# W601X.net
KiCad netlist of a schematic drawn in EAGLE
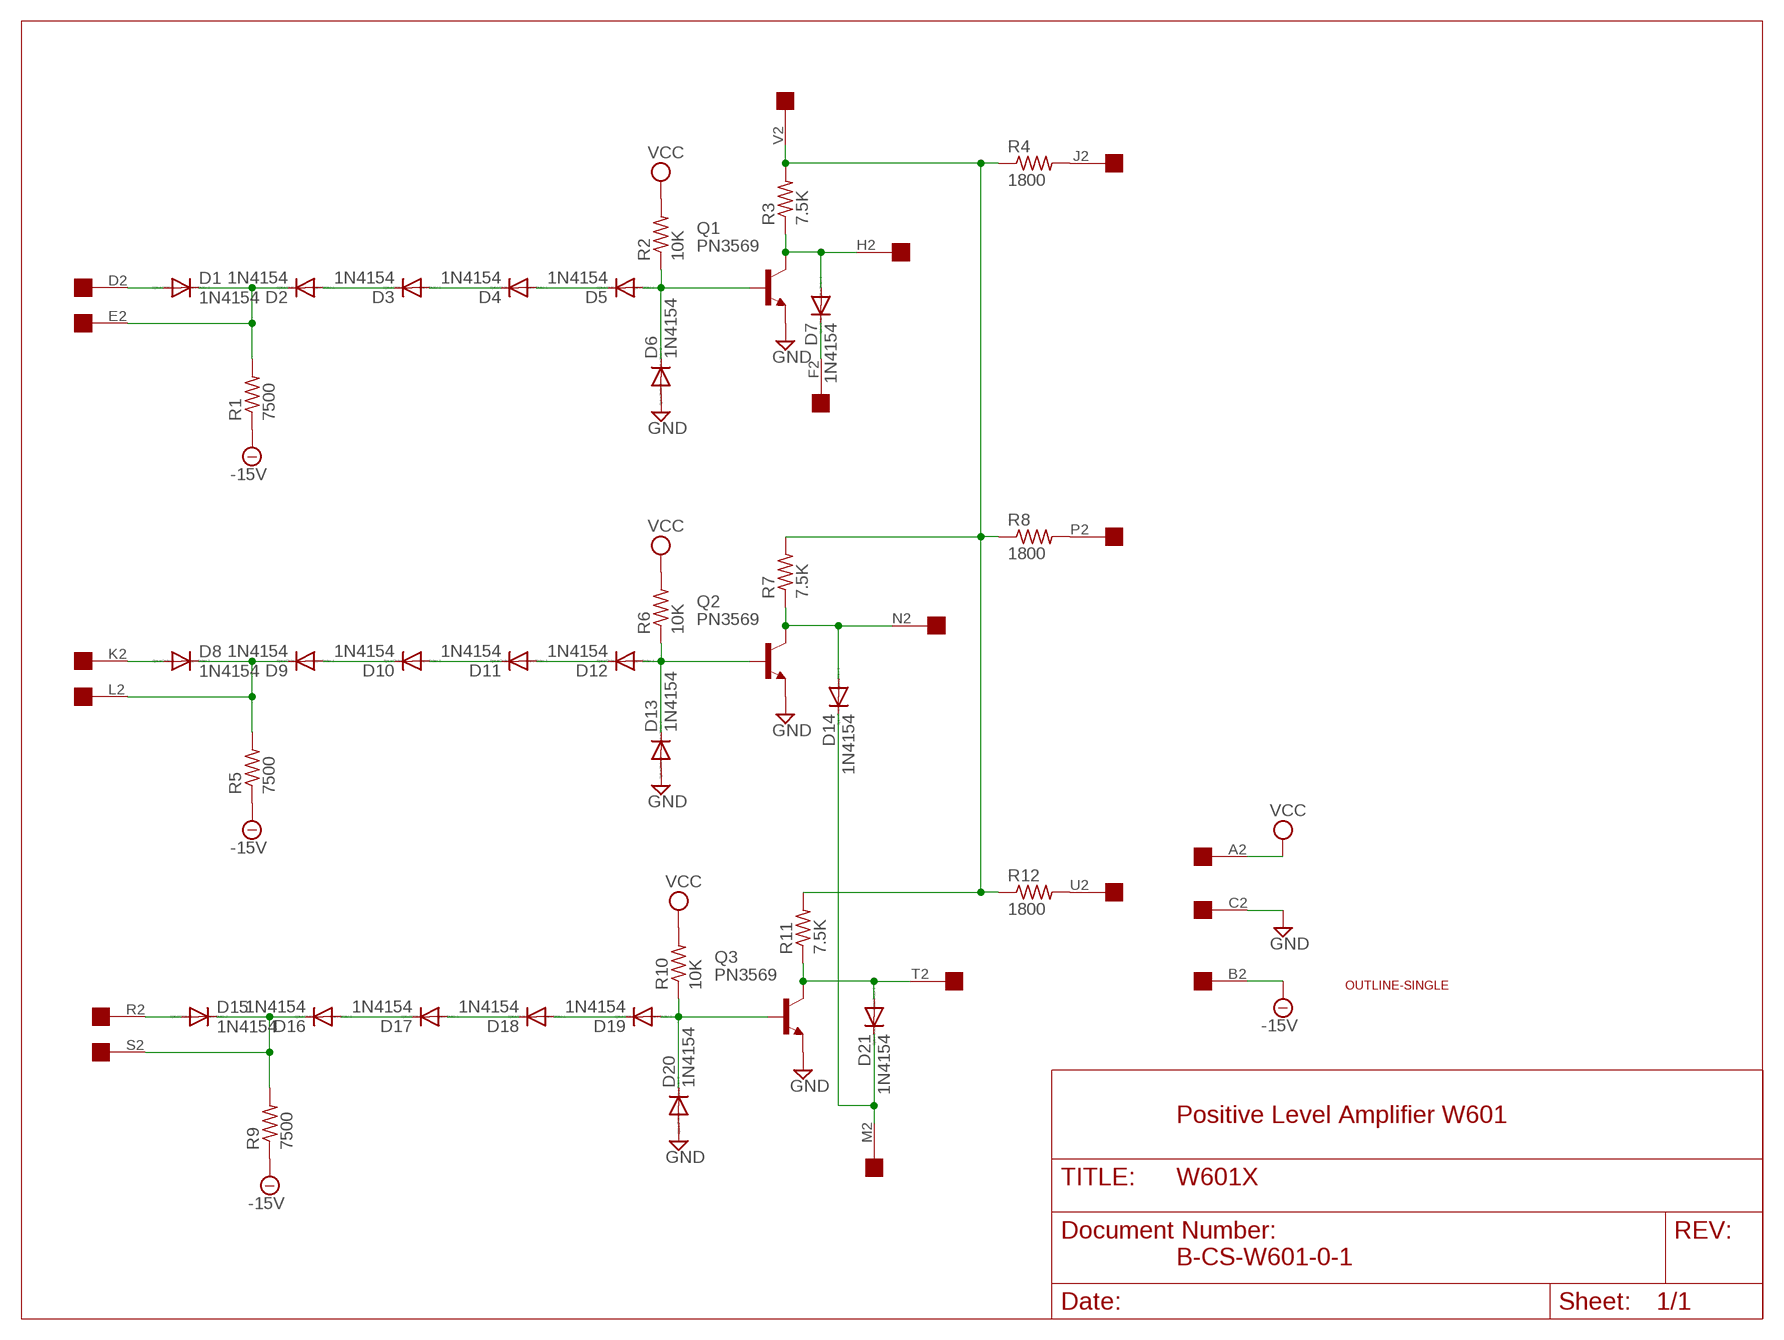
[diagram p0: schematic, sheet 1]

(export (version "E")
  (design (tool "Eeschema 10.0.6"))
  (components
    (comp (ref "D1")
      (value "1N4154")
      (footprint "eagle-import:DO35-10")
      (libsource (lib "eagle-import") (part "DIODE-DO35-10"))
    )
    (comp (ref "D2")
      (value "1N4154")
      (footprint "eagle-import:DO35-10")
      (libsource (lib "eagle-import") (part "DIODE-DO35-10"))
    )
    (comp (ref "D3")
      (value "1N4154")
      (footprint "eagle-import:DO35-10")
      (libsource (lib "eagle-import") (part "DIODE-DO35-10"))
    )
    (comp (ref "D4")
      (value "1N4154")
      (footprint "eagle-import:DO35-10")
      (libsource (lib "eagle-import") (part "DIODE-DO35-10"))
    )
    (comp (ref "D5")
      (value "1N4154")
      (footprint "eagle-import:DO35-10")
      (libsource (lib "eagle-import") (part "DIODE-DO35-10"))
    )
    (comp (ref "D6")
      (value "1N4154")
      (footprint "eagle-import:DO35-10")
      (libsource (lib "eagle-import") (part "DIODE-DO35-10"))
    )
    (comp (ref "D7")
      (value "1N4154")
      (footprint "eagle-import:DO35-10")
      (libsource (lib "eagle-import") (part "DIODE-DO35-10"))
    )
    (comp (ref "D8")
      (value "1N4154")
      (footprint "eagle-import:DO35-10")
      (libsource (lib "eagle-import") (part "DIODE-DO35-10"))
    )
    (comp (ref "D9")
      (value "1N4154")
      (footprint "eagle-import:DO35-10")
      (libsource (lib "eagle-import") (part "DIODE-DO35-10"))
    )
    (comp (ref "D10")
      (value "1N4154")
      (footprint "eagle-import:DO35-10")
      (libsource (lib "eagle-import") (part "DIODE-DO35-10"))
    )
    (comp (ref "D11")
      (value "1N4154")
      (footprint "eagle-import:DO35-10")
      (libsource (lib "eagle-import") (part "DIODE-DO35-10"))
    )
    (comp (ref "D12")
      (value "1N4154")
      (footprint "eagle-import:DO35-10")
      (libsource (lib "eagle-import") (part "DIODE-DO35-10"))
    )
    (comp (ref "D13")
      (value "1N4154")
      (footprint "eagle-import:DO35-10")
      (libsource (lib "eagle-import") (part "DIODE-DO35-10"))
    )
    (comp (ref "D14")
      (value "1N4154")
      (footprint "eagle-import:DO35-10")
      (libsource (lib "eagle-import") (part "DIODE-DO35-10"))
    )
    (comp (ref "D15")
      (value "1N4154")
      (footprint "eagle-import:DO35-10")
      (libsource (lib "eagle-import") (part "DIODE-DO35-10"))
    )
    (comp (ref "D16")
      (value "1N4154")
      (footprint "eagle-import:DO35-10")
      (libsource (lib "eagle-import") (part "DIODE-DO35-10"))
    )
    (comp (ref "D17")
      (value "1N4154")
      (footprint "eagle-import:DO35-10")
      (libsource (lib "eagle-import") (part "DIODE-DO35-10"))
    )
    (comp (ref "D18")
      (value "1N4154")
      (footprint "eagle-import:DO35-10")
      (libsource (lib "eagle-import") (part "DIODE-DO35-10"))
    )
    (comp (ref "D19")
      (value "1N4154")
      (footprint "eagle-import:DO35-10")
      (libsource (lib "eagle-import") (part "DIODE-DO35-10"))
    )
    (comp (ref "D20")
      (value "1N4154")
      (footprint "eagle-import:DO35-10")
      (libsource (lib "eagle-import") (part "DIODE-DO35-10"))
    )
    (comp (ref "D21")
      (value "1N4154")
      (footprint "eagle-import:DO35-10")
      (libsource (lib "eagle-import") (part "DIODE-DO35-10"))
    )
    (comp (ref "Q1")
      (value "PN3569")
      (footprint "eagle-import:TO5")
      (libsource (lib "eagle-import") (part "-NPN-TO5"))
    )
    (comp (ref "Q2")
      (value "PN3569")
      (footprint "eagle-import:TO5")
      (libsource (lib "eagle-import") (part "-NPN-TO5"))
    )
    (comp (ref "Q3")
      (value "PN3569")
      (footprint "eagle-import:TO5")
      (libsource (lib "eagle-import") (part "-NPN-TO5"))
    )
    (comp (ref "R1")
      (value "7500")
      (footprint "eagle-import:0207_10")
      (libsource (lib "eagle-import") (part "R-US_0207/10"))
    )
    (comp (ref "R2")
      (value "10K")
      (footprint "eagle-import:0207_10")
      (libsource (lib "eagle-import") (part "R-US_0207/10"))
    )
    (comp (ref "R3")
      (value "7.5K")
      (footprint "eagle-import:0207_10")
      (libsource (lib "eagle-import") (part "R-US_0207/10"))
    )
    (comp (ref "R4")
      (value "1800")
      (footprint "eagle-import:0207_10")
      (libsource (lib "eagle-import") (part "R-US_0207/10"))
    )
    (comp (ref "R5")
      (value "7500")
      (footprint "eagle-import:0207_10")
      (libsource (lib "eagle-import") (part "R-US_0207/10"))
    )
    (comp (ref "R6")
      (value "10K")
      (footprint "eagle-import:0207_10")
      (libsource (lib "eagle-import") (part "R-US_0207/10"))
    )
    (comp (ref "R7")
      (value "7.5K")
      (footprint "eagle-import:0207_10")
      (libsource (lib "eagle-import") (part "R-US_0207/10"))
    )
    (comp (ref "R8")
      (value "1800")
      (footprint "eagle-import:0207_10")
      (libsource (lib "eagle-import") (part "R-US_0207/10"))
    )
    (comp (ref "R9")
      (value "7500")
      (footprint "eagle-import:0207_10")
      (libsource (lib "eagle-import") (part "R-US_0207/10"))
    )
    (comp (ref "R10")
      (value "10K")
      (footprint "eagle-import:0207_10")
      (libsource (lib "eagle-import") (part "R-US_0207/10"))
    )
    (comp (ref "R11")
      (value "7.5K")
      (footprint "eagle-import:0207_10")
      (libsource (lib "eagle-import") (part "R-US_0207/10"))
    )
    (comp (ref "R12")
      (value "1800")
      (footprint "eagle-import:0207_10")
      (libsource (lib "eagle-import") (part "R-US_0207/10"))
    )
    (comp (ref "U$1")
      (value "OUTLINE-SINGLE")
      (footprint "eagle-import:SINGLE")
      (libsource (lib "eagle-import") (part "OUTLINE-SINGLE"))
    )
    (comp (ref "U$2")
      (value "EDGE-1")
      (footprint "eagle-import:EDGE-CON1")
      (libsource (lib "eagle-import") (part "EDGE-1"))
    )
  )
  (nets
    (net (code "1") (name "-15V") (class "Default")
      (node (ref "R1") (pin "1") (pinfunction "1_1") (pintype "passive"))
      (node (ref "R5") (pin "1") (pinfunction "1_1") (pintype "passive"))
      (node (ref "R9") (pin "1") (pinfunction "1_1") (pintype "passive"))
      (node (ref "U$2") (pin "B2") (pinfunction "1_B2") (pintype "bidirectional"))
    )
    (net (code "2") (name "GND") (class "Default")
      (node (ref "D13") (pin "A") (pinfunction "A_A") (pintype "passive"))
      (node (ref "D20") (pin "A") (pinfunction "A_A") (pintype "passive"))
      (node (ref "D6") (pin "A") (pinfunction "A_A") (pintype "passive"))
      (node (ref "Q1") (pin "1") (pinfunction "E_1") (pintype "passive"))
      (node (ref "Q2") (pin "1") (pinfunction "E_1") (pintype "passive"))
      (node (ref "Q3") (pin "1") (pinfunction "E_1") (pintype "passive"))
      (node (ref "U$2") (pin "C2") (pinfunction "1_C2") (pintype "bidirectional"))
    )
    (net (code "3") (name "Net-(D2-PadA)") (class "Default")
      (node (ref "D2") (pin "A") (pinfunction "A_A") (pintype "passive"))
      (node (ref "D3") (pin "C") (pinfunction "C_C") (pintype "passive"))
    )
    (net (code "4") (name "Net-(D3-PadA)") (class "Default")
      (node (ref "D3") (pin "A") (pinfunction "A_A") (pintype "passive"))
      (node (ref "D4") (pin "C") (pinfunction "C_C") (pintype "passive"))
    )
    (net (code "5") (name "Net-(D4-PadA)") (class "Default")
      (node (ref "D4") (pin "A") (pinfunction "A_A") (pintype "passive"))
      (node (ref "D5") (pin "C") (pinfunction "C_C") (pintype "passive"))
    )
    (net (code "6") (name "Net-(D10-PadA)") (class "Default")
      (node (ref "D10") (pin "A") (pinfunction "A_A") (pintype "passive"))
      (node (ref "D11") (pin "C") (pinfunction "C_C") (pintype "passive"))
    )
    (net (code "7") (name "Net-(D10-PadC)") (class "Default")
      (node (ref "D10") (pin "C") (pinfunction "C_C") (pintype "passive"))
      (node (ref "D9") (pin "A") (pinfunction "A_A") (pintype "passive"))
    )
    (net (code "8") (name "Net-(D11-PadA)") (class "Default")
      (node (ref "D11") (pin "A") (pinfunction "A_A") (pintype "passive"))
      (node (ref "D12") (pin "C") (pinfunction "C_C") (pintype "passive"))
    )
    (net (code "9") (name "Net-(D16-PadA)") (class "Default")
      (node (ref "D16") (pin "A") (pinfunction "A_A") (pintype "passive"))
      (node (ref "D17") (pin "C") (pinfunction "C_C") (pintype "passive"))
    )
    (net (code "10") (name "Net-(D17-PadA)") (class "Default")
      (node (ref "D17") (pin "A") (pinfunction "A_A") (pintype "passive"))
      (node (ref "D18") (pin "C") (pinfunction "C_C") (pintype "passive"))
    )
    (net (code "11") (name "Net-(D18-PadA)") (class "Default")
      (node (ref "D18") (pin "A") (pinfunction "A_A") (pintype "passive"))
      (node (ref "D19") (pin "C") (pinfunction "C_C") (pintype "passive"))
    )
    (net (code "12") (name "Net-(Q1-B)") (class "Default")
      (node (ref "D5") (pin "A") (pinfunction "A_A") (pintype "passive"))
      (node (ref "D6") (pin "C") (pinfunction "C_C") (pintype "passive"))
      (node (ref "Q1") (pin "2") (pinfunction "B_2") (pintype "passive"))
      (node (ref "R2") (pin "1") (pinfunction "1_1") (pintype "passive"))
    )
    (net (code "13") (name "Net-(Q1-C)") (class "Default")
      (node (ref "D7") (pin "A") (pinfunction "A_A") (pintype "passive"))
      (node (ref "Q1") (pin "3") (pinfunction "C_3") (pintype "passive"))
      (node (ref "R3") (pin "1") (pinfunction "1_1") (pintype "passive"))
      (node (ref "U$2") (pin "H2") (pinfunction "1_H2") (pintype "bidirectional"))
    )
    (net (code "14") (name "Net-(Q2-B)") (class "Default")
      (node (ref "D12") (pin "A") (pinfunction "A_A") (pintype "passive"))
      (node (ref "D13") (pin "C") (pinfunction "C_C") (pintype "passive"))
      (node (ref "Q2") (pin "2") (pinfunction "B_2") (pintype "passive"))
      (node (ref "R6") (pin "1") (pinfunction "1_1") (pintype "passive"))
    )
    (net (code "15") (name "Net-(Q2-C)") (class "Default")
      (node (ref "D14") (pin "A") (pinfunction "A_A") (pintype "passive"))
      (node (ref "Q2") (pin "3") (pinfunction "C_3") (pintype "passive"))
      (node (ref "R7") (pin "1") (pinfunction "1_1") (pintype "passive"))
      (node (ref "U$2") (pin "N2") (pinfunction "1_N2") (pintype "bidirectional"))
    )
    (net (code "16") (name "Net-(Q3-B)") (class "Default")
      (node (ref "D19") (pin "A") (pinfunction "A_A") (pintype "passive"))
      (node (ref "D20") (pin "C") (pinfunction "C_C") (pintype "passive"))
      (node (ref "Q3") (pin "2") (pinfunction "B_2") (pintype "passive"))
      (node (ref "R10") (pin "1") (pinfunction "1_1") (pintype "passive"))
    )
    (net (code "17") (name "Net-(Q3-C)") (class "Default")
      (node (ref "D21") (pin "A") (pinfunction "A_A") (pintype "passive"))
      (node (ref "Q3") (pin "3") (pinfunction "C_3") (pintype "passive"))
      (node (ref "R11") (pin "1") (pinfunction "1_1") (pintype "passive"))
      (node (ref "U$2") (pin "T2") (pinfunction "1_T2") (pintype "bidirectional"))
    )
    (net (code "18") (name "Net-(U$2D-1)") (class "Default")
      (node (ref "D1") (pin "A") (pinfunction "A_A") (pintype "passive"))
      (node (ref "U$2") (pin "D2") (pinfunction "1_D2") (pintype "bidirectional"))
    )
    (net (code "19") (name "Net-(U$2E-1)") (class "Default")
      (node (ref "D1") (pin "C") (pinfunction "C_C") (pintype "passive"))
      (node (ref "D2") (pin "C") (pinfunction "C_C") (pintype "passive"))
      (node (ref "R1") (pin "2") (pinfunction "2_2") (pintype "passive"))
      (node (ref "U$2") (pin "E2") (pinfunction "1_E2") (pintype "bidirectional"))
    )
    (net (code "20") (name "Net-(U$2F-1)") (class "Default")
      (node (ref "D7") (pin "C") (pinfunction "C_C") (pintype "passive"))
      (node (ref "U$2") (pin "F2") (pinfunction "1_F2") (pintype "bidirectional"))
    )
    (net (code "21") (name "Net-(U$2H-1)") (class "Default")
      (node (ref "R4") (pin "2") (pinfunction "2_2") (pintype "passive"))
      (node (ref "U$2") (pin "J2") (pinfunction "1_J2") (pintype "bidirectional"))
    )
    (net (code "22") (name "Net-(U$2I-1)") (class "Default")
      (node (ref "D8") (pin "A") (pinfunction "A_A") (pintype "passive"))
      (node (ref "U$2") (pin "K2") (pinfunction "1_K2") (pintype "bidirectional"))
    )
    (net (code "23") (name "Net-(U$2J-1)") (class "Default")
      (node (ref "D8") (pin "C") (pinfunction "C_C") (pintype "passive"))
      (node (ref "D9") (pin "C") (pinfunction "C_C") (pintype "passive"))
      (node (ref "R5") (pin "2") (pinfunction "2_2") (pintype "passive"))
      (node (ref "U$2") (pin "L2") (pinfunction "1_L2") (pintype "bidirectional"))
    )
    (net (code "24") (name "Net-(U$2K-1)") (class "Default")
      (node (ref "D14") (pin "C") (pinfunction "C_C") (pintype "passive"))
      (node (ref "D21") (pin "C") (pinfunction "C_C") (pintype "passive"))
      (node (ref "U$2") (pin "M2") (pinfunction "1_M2") (pintype "bidirectional"))
    )
    (net (code "25") (name "Net-(U$2M-1)") (class "Default")
      (node (ref "R8") (pin "2") (pinfunction "2_2") (pintype "passive"))
      (node (ref "U$2") (pin "P2") (pinfunction "1_P2") (pintype "bidirectional"))
    )
    (net (code "26") (name "Net-(U$2N-1)") (class "Default")
      (node (ref "D15") (pin "A") (pinfunction "A_A") (pintype "passive"))
      (node (ref "U$2") (pin "R2") (pinfunction "1_R2") (pintype "bidirectional"))
    )
    (net (code "27") (name "Net-(U$2O-1)") (class "Default")
      (node (ref "D15") (pin "C") (pinfunction "C_C") (pintype "passive"))
      (node (ref "D16") (pin "C") (pinfunction "C_C") (pintype "passive"))
      (node (ref "R9") (pin "2") (pinfunction "2_2") (pintype "passive"))
      (node (ref "U$2") (pin "S2") (pinfunction "1_S2") (pintype "bidirectional"))
    )
    (net (code "28") (name "Net-(U$2Q-1)") (class "Default")
      (node (ref "R12") (pin "2") (pinfunction "2_2") (pintype "passive"))
      (node (ref "U$2") (pin "U2") (pinfunction "1_U2") (pintype "bidirectional"))
    )
    (net (code "29") (name "Net-(U$2R-1)") (class "Default")
      (node (ref "R11") (pin "2") (pinfunction "2_2") (pintype "passive"))
      (node (ref "R12") (pin "1") (pinfunction "1_1") (pintype "passive"))
      (node (ref "R3") (pin "2") (pinfunction "2_2") (pintype "passive"))
      (node (ref "R4") (pin "1") (pinfunction "1_1") (pintype "passive"))
      (node (ref "R7") (pin "2") (pinfunction "2_2") (pintype "passive"))
      (node (ref "R8") (pin "1") (pinfunction "1_1") (pintype "passive"))
      (node (ref "U$2") (pin "V2") (pinfunction "1_V2") (pintype "bidirectional"))
    )
    (net (code "30") (name "VCC") (class "Default")
      (node (ref "R10") (pin "2") (pinfunction "2_2") (pintype "passive"))
      (node (ref "R2") (pin "2") (pinfunction "2_2") (pintype "passive"))
      (node (ref "R6") (pin "2") (pinfunction "2_2") (pintype "passive"))
      (node (ref "U$2") (pin "A2") (pinfunction "1_A2") (pintype "bidirectional"))
    )
  )
)
